# ECU_Interface.net
KiCad netlist of a schematic drawn in Altium Designer
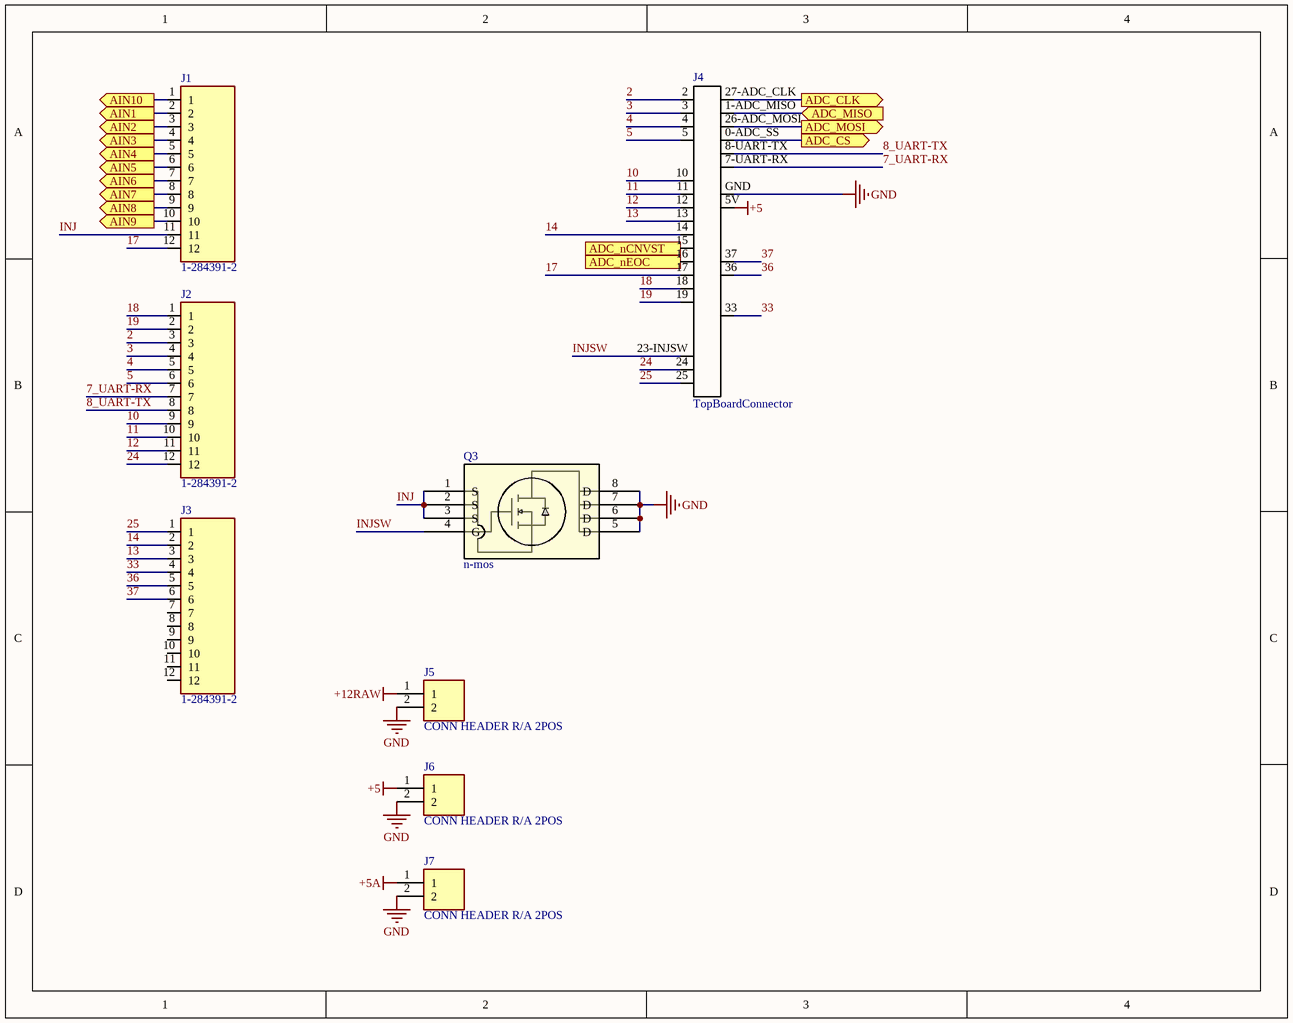
[diagram p0: ECU_Interface.SchDoc]

(export (version "E")
  (design (tool "Eeschema 10.0.6"))
  (components
    (comp (ref "J1")
      (value "1-284391-2")
      (footprint "TE_1-284391-2:TE_1-284391-2")
      (description "Conn Eurostyle Block F 12 POS 3.5mm Solder ST Thru-Hole 12A/Contact Box")
      (fields (field (name "MF") "TE Connectivity"))
      (libsource (lib "1-284391-2") (part "1-284391-2"))
    )
    (comp (ref "J2")
      (value "1-284391-2")
      (footprint "TE_1-284391-2:TE_1-284391-2")
      (description "Conn Eurostyle Block F 12 POS 3.5mm Solder ST Thru-Hole 12A/Contact Box")
      (fields (field (name "MF") "TE Connectivity"))
      (libsource (lib "1-284391-2") (part "1-284391-2"))
    )
    (comp (ref "J3")
      (value "1-284391-2")
      (footprint "TE_1-284391-2:TE_1-284391-2")
      (description "Conn Eurostyle Block F 12 POS 3.5mm Solder ST Thru-Hole 12A/Contact Box")
      (fields (field (name "MF") "TE Connectivity"))
      (libsource (lib "1-284391-2") (part "1-284391-2"))
    )
    (comp (ref "J4")
      (value "TopBoardConnector")
      (footprint "TopBoardConnector")
      (description "Connection to the bottom board")
      (libsource (lib "TopBoardConnector") (part "TopBoardConnector"))
    )
    (comp (ref "J5")
      (value "CONN HEADER R/A 2POS")
      (footprint "2 POS MOLEX")
      (fields (field (name "MANUFACTURER") "Molex") (field (name "MANUFACTURER PART NUMBER") "1724480002"))
      (libsource (lib "1724480002") (part "1724480002"))
    )
    (comp (ref "J6")
      (value "CONN HEADER R/A 2POS")
      (footprint "2 POS MOLEX")
      (fields (field (name "MANUFACTURER") "Molex") (field (name "MANUFACTURER PART NUMBER") "1724480002"))
      (libsource (lib "1724480002") (part "1724480002"))
    )
    (comp (ref "J7")
      (value "CONN HEADER R/A 2POS")
      (footprint "2 POS MOLEX")
      (fields (field (name "MANUFACTURER") "Molex") (field (name "MANUFACTURER PART NUMBER") "1724480002"))
      (libsource (lib "1724480002") (part "1724480002"))
    )
    (comp (ref "Q3")
      (value "n-mos")
      (footprint "D0008A-IPC_A")
      (description "MOSFET MOSFETBVDSS: 25V-30V")
      (libsource (lib "DMN3007LSSQ-13") (part "DMN3007LSSQ-13"))
    )
  )
  (nets
    (net (code "1") (name "+5") (class "Default")
      (node (ref "J4") (pin "5V") (pinfunction "5V_5V") (pintype "passive"))
      (node (ref "J6") (pin "1") (pinfunction "1_1") (pintype "passive"))
    )
    (net (code "2") (name "+5A") (class "Default")
      (node (ref "J7") (pin "1") (pinfunction "1_1") (pintype "passive"))
    )
    (net (code "3") (name "+12RAW") (class "Default")
      (node (ref "J5") (pin "1") (pinfunction "1_1") (pintype "passive"))
    )
    (net (code "4") (name "/2") (class "Default")
      (node (ref "J2") (pin "3") (pinfunction "3_3") (pintype "passive"))
      (node (ref "J4") (pin "2") (pinfunction "2_2") (pintype "passive"))
    )
    (net (code "5") (name "/3") (class "Default")
      (node (ref "J2") (pin "4") (pinfunction "4_4") (pintype "passive"))
      (node (ref "J4") (pin "3") (pinfunction "3_3") (pintype "passive"))
    )
    (net (code "6") (name "/4") (class "Default")
      (node (ref "J2") (pin "5") (pinfunction "5_5") (pintype "passive"))
      (node (ref "J4") (pin "4") (pinfunction "4_4") (pintype "passive"))
    )
    (net (code "7") (name "/5") (class "Default")
      (node (ref "J2") (pin "6") (pinfunction "6_6") (pintype "passive"))
      (node (ref "J4") (pin "5") (pinfunction "5_5") (pintype "passive"))
    )
    (net (code "8") (name "/7_UART-RX") (class "Default")
      (node (ref "J2") (pin "7") (pinfunction "7_7") (pintype "passive"))
      (node (ref "J4") (pin "7-UART-RX") (pinfunction "8-UART-RX_7-UART-RX") (pintype "passive"))
    )
    (net (code "9") (name "/8_UART-TX") (class "Default")
      (node (ref "J2") (pin "8") (pinfunction "8_8") (pintype "passive"))
      (node (ref "J4") (pin "8-UART-TX") (pinfunction "8-UART-TX_8-UART-TX") (pintype "passive"))
    )
    (net (code "10") (name "/10") (class "Default")
      (node (ref "J2") (pin "9") (pinfunction "9_9") (pintype "passive"))
      (node (ref "J4") (pin "10") (pinfunction "10_10") (pintype "passive"))
    )
    (net (code "11") (name "/11") (class "Default")
      (node (ref "J2") (pin "10") (pinfunction "10_10") (pintype "passive"))
      (node (ref "J4") (pin "11") (pinfunction "11_11") (pintype "passive"))
    )
    (net (code "12") (name "/12") (class "Default")
      (node (ref "J2") (pin "11") (pinfunction "11_11") (pintype "passive"))
      (node (ref "J4") (pin "12") (pinfunction "12_12") (pintype "passive"))
    )
    (net (code "13") (name "/13") (class "Default")
      (node (ref "J3") (pin "3") (pinfunction "3_3") (pintype "passive"))
      (node (ref "J4") (pin "13") (pinfunction "13_13") (pintype "passive"))
    )
    (net (code "14") (name "/14") (class "Default")
      (node (ref "J3") (pin "2") (pinfunction "2_2") (pintype "passive"))
      (node (ref "J4") (pin "14") (pinfunction "14_14") (pintype "passive"))
    )
    (net (code "15") (name "/17") (class "Default")
      (node (ref "J1") (pin "12") (pinfunction "12_12") (pintype "passive"))
      (node (ref "J4") (pin "17") (pinfunction "17_17") (pintype "passive"))
    )
    (net (code "16") (name "/18") (class "Default")
      (node (ref "J2") (pin "1") (pinfunction "1_1") (pintype "passive"))
      (node (ref "J4") (pin "18") (pinfunction "18_18") (pintype "passive"))
    )
    (net (code "17") (name "/19") (class "Default")
      (node (ref "J2") (pin "2") (pinfunction "2_2") (pintype "passive"))
      (node (ref "J4") (pin "19") (pinfunction "19_19") (pintype "passive"))
    )
    (net (code "18") (name "/24") (class "Default")
      (node (ref "J2") (pin "12") (pinfunction "12_12") (pintype "passive"))
      (node (ref "J4") (pin "24") (pinfunction "24_24") (pintype "passive"))
    )
    (net (code "19") (name "/25") (class "Default")
      (node (ref "J3") (pin "1") (pinfunction "1_1") (pintype "passive"))
      (node (ref "J4") (pin "25") (pinfunction "25_25") (pintype "passive"))
    )
    (net (code "20") (name "/33") (class "Default")
      (node (ref "J3") (pin "4") (pinfunction "4_4") (pintype "passive"))
      (node (ref "J4") (pin "33") (pinfunction "33_33") (pintype "passive"))
    )
    (net (code "21") (name "/36") (class "Default")
      (node (ref "J3") (pin "5") (pinfunction "5_5") (pintype "passive"))
      (node (ref "J4") (pin "36") (pinfunction "36_36") (pintype "passive"))
    )
    (net (code "22") (name "/37") (class "Default")
      (node (ref "J3") (pin "6") (pinfunction "6_6") (pintype "passive"))
      (node (ref "J4") (pin "37") (pinfunction "37_37") (pintype "passive"))
    )
    (net (code "23") (name "/ADC_CLK") (class "Default")
      (node (ref "J4") (pin "27-ADC_CLK") (pinfunction "27-ADC_CLK_27-ADC_CLK") (pintype "passive"))
    )
    (net (code "24") (name "/ADC_CS") (class "Default")
      (node (ref "J4") (pin "0-ADC_SS") (pinfunction "0-ADC_SS_0-ADC_SS") (pintype "passive"))
    )
    (net (code "25") (name "/ADC_MISO") (class "Default")
      (node (ref "J4") (pin "1-ADC_MISO") (pinfunction "1-ADC_MISO_1-ADC_MISO") (pintype "passive"))
    )
    (net (code "26") (name "/ADC_MOSI") (class "Default")
      (node (ref "J4") (pin "26-ADC_MOSI") (pinfunction "26-ADC_MOSI_26-ADC_MOSI") (pintype "passive"))
    )
    (net (code "27") (name "/ADC_nCNVST") (class "Default")
      (node (ref "J4") (pin "15") (pinfunction "15_15") (pintype "passive"))
    )
    (net (code "28") (name "/ADC_nEOC") (class "Default")
      (node (ref "J4") (pin "16") (pinfunction "16_16") (pintype "passive"))
    )
    (net (code "29") (name "/AIN1") (class "Default")
      (node (ref "J1") (pin "2") (pinfunction "2_2") (pintype "passive"))
    )
    (net (code "30") (name "/AIN2") (class "Default")
      (node (ref "J1") (pin "3") (pinfunction "3_3") (pintype "passive"))
    )
    (net (code "31") (name "/AIN3") (class "Default")
      (node (ref "J1") (pin "4") (pinfunction "4_4") (pintype "passive"))
    )
    (net (code "32") (name "/AIN4") (class "Default")
      (node (ref "J1") (pin "5") (pinfunction "5_5") (pintype "passive"))
    )
    (net (code "33") (name "/AIN5") (class "Default")
      (node (ref "J1") (pin "6") (pinfunction "6_6") (pintype "passive"))
    )
    (net (code "34") (name "/AIN6") (class "Default")
      (node (ref "J1") (pin "7") (pinfunction "7_7") (pintype "passive"))
    )
    (net (code "35") (name "/AIN7") (class "Default")
      (node (ref "J1") (pin "8") (pinfunction "8_8") (pintype "passive"))
    )
    (net (code "36") (name "/AIN8") (class "Default")
      (node (ref "J1") (pin "9") (pinfunction "9_9") (pintype "passive"))
    )
    (net (code "37") (name "/AIN9") (class "Default")
      (node (ref "J1") (pin "10") (pinfunction "10_10") (pintype "passive"))
    )
    (net (code "38") (name "/AIN10") (class "Default")
      (node (ref "J1") (pin "1") (pinfunction "1_1") (pintype "passive"))
    )
    (net (code "39") (name "/INJ") (class "Default")
      (node (ref "J1") (pin "11") (pinfunction "11_11") (pintype "passive"))
      (node (ref "Q3") (pin "1") (pinfunction "S_1") (pintype "passive"))
      (node (ref "Q3") (pin "2") (pinfunction "S_2") (pintype "passive"))
      (node (ref "Q3") (pin "3") (pinfunction "S_3") (pintype "passive"))
    )
    (net (code "40") (name "/INJSW") (class "Default")
      (node (ref "J4") (pin "23-INJSW") (pinfunction "23-INJSW_23-INJSW") (pintype "passive"))
      (node (ref "Q3") (pin "4") (pinfunction "G_4") (pintype "passive"))
    )
    (net (code "41") (name "GND") (class "Default")
      (node (ref "J4") (pin "GND") (pinfunction "GND_GND") (pintype "passive"))
      (node (ref "J5") (pin "2") (pinfunction "2_2") (pintype "passive"))
      (node (ref "J6") (pin "2") (pinfunction "2_2") (pintype "passive"))
      (node (ref "J7") (pin "2") (pinfunction "2_2") (pintype "passive"))
      (node (ref "Q3") (pin "5") (pinfunction "D_5") (pintype "passive"))
      (node (ref "Q3") (pin "6") (pinfunction "D_6") (pintype "passive"))
      (node (ref "Q3") (pin "7") (pinfunction "D_7") (pintype "passive"))
      (node (ref "Q3") (pin "8") (pinfunction "D_8") (pintype "passive"))
    )
    (net (code "42") (name "unconnected-(J3-Pad7)") (class "Default")
      (node (ref "J3") (pin "7") (pinfunction "7_7") (pintype "passive"))
    )
    (net (code "43") (name "unconnected-(J3-Pad8)") (class "Default")
      (node (ref "J3") (pin "8") (pinfunction "8_8") (pintype "passive"))
    )
    (net (code "44") (name "unconnected-(J3-Pad9)") (class "Default")
      (node (ref "J3") (pin "9") (pinfunction "9_9") (pintype "passive"))
    )
    (net (code "45") (name "unconnected-(J3-Pad10)") (class "Default")
      (node (ref "J3") (pin "10") (pinfunction "10_10") (pintype "passive"))
    )
    (net (code "46") (name "unconnected-(J3-Pad11)") (class "Default")
      (node (ref "J3") (pin "11") (pinfunction "11_11") (pintype "passive"))
    )
    (net (code "47") (name "unconnected-(J3-Pad12)") (class "Default")
      (node (ref "J3") (pin "12") (pinfunction "12_12") (pintype "passive"))
    )
  )
)
